# 10_LMS3_RF.net
KiCad netlist of a schematic drawn in Altium Designer
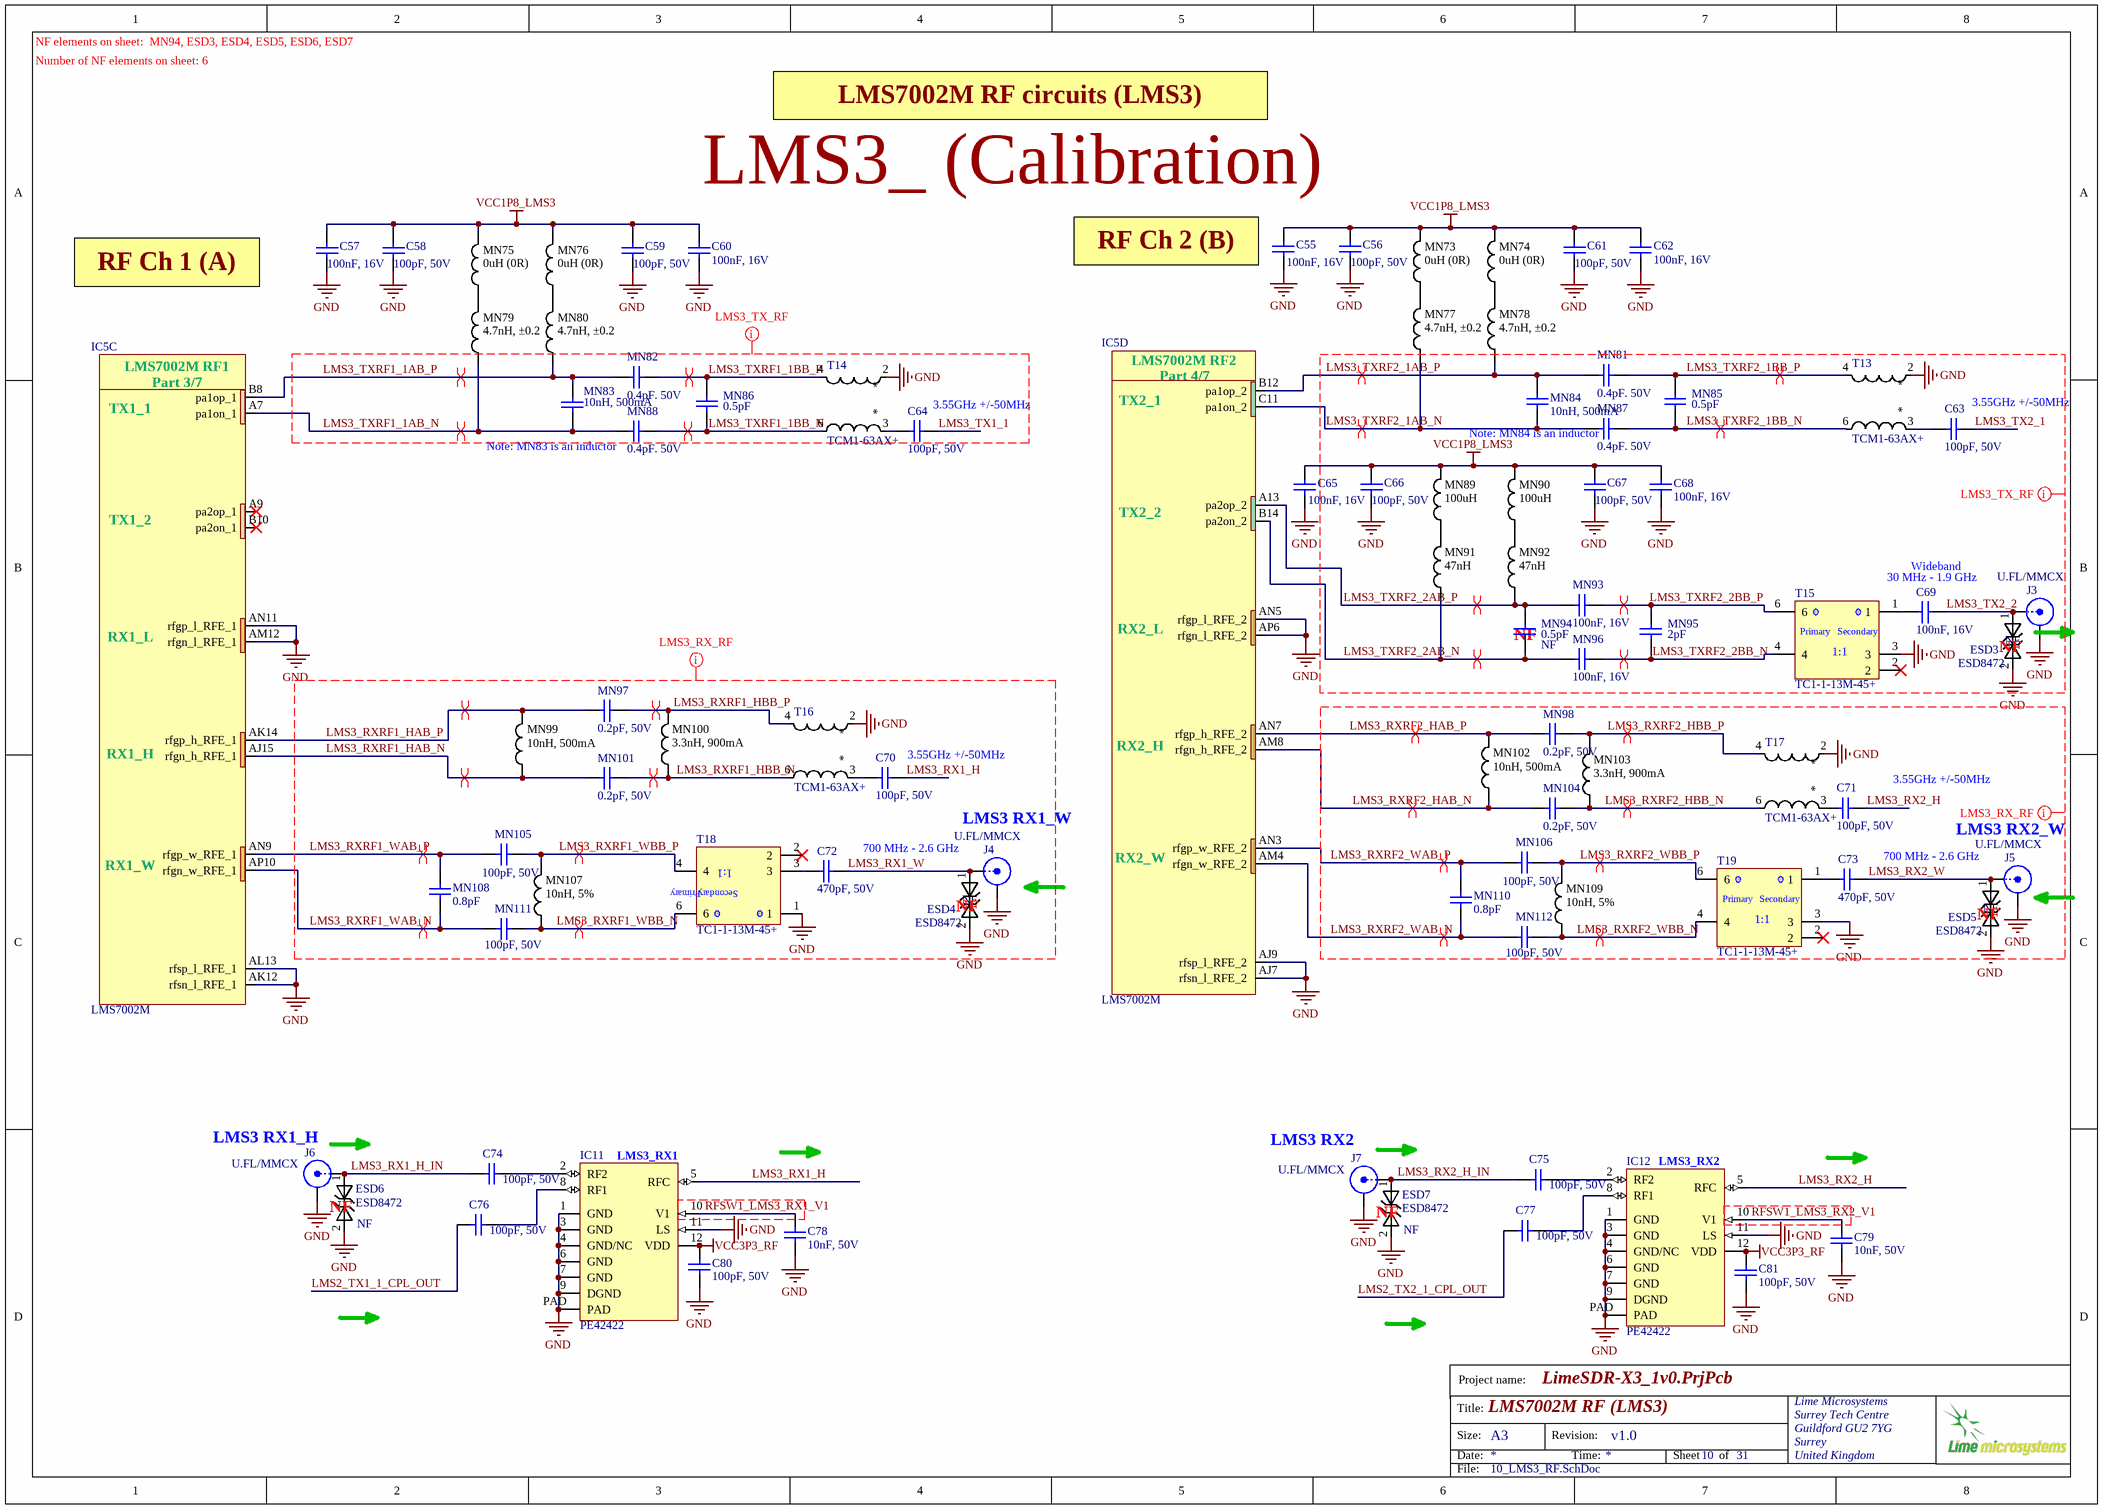
[diagram p0: 10_LMS3_RF.SchDoc]

(export (version "E")
  (design (tool "Eeschema 10.0.6"))
  (components
    (comp (ref "C55")
      (value "100nF, 16V")
      (footprint "CAP0402")
      (fields (field (name "MANUFACTURER") "Murata Electronics") (field (name "TOLERANCE") "10 %"))
      (libsource (lib "") (part "Cap_0402_3"))
    )
    (comp (ref "C56")
      (value "100pF, 50V")
      (footprint "CAP0402")
      (fields (field (name "MANUFACTURER") "Yageo") (field (name "TOLERANCE") "±5%"))
      (libsource (lib "LimeMicroAltiumLib_schLib") (part "Cap_0402"))
    )
    (comp (ref "C57")
      (value "100nF, 16V")
      (footprint "CAP0402")
      (fields (field (name "MANUFACTURER") "Murata Electronics") (field (name "TOLERANCE") "10 %"))
      (libsource (lib "") (part "Cap_0402_7"))
    )
    (comp (ref "C58")
      (value "100pF, 50V")
      (footprint "CAP0402")
      (fields (field (name "MANUFACTURER") "Yageo") (field (name "TOLERANCE") "±5%"))
      (libsource (lib "LimeMicroAltiumLib_schLib") (part "Cap_0402"))
    )
    (comp (ref "C59")
      (value "100pF, 50V")
      (footprint "CAP0402")
      (fields (field (name "MANUFACTURER") "Yageo") (field (name "TOLERANCE") "±5%"))
      (libsource (lib "LimeMicroAltiumLib_schLib") (part "Cap_0402"))
    )
    (comp (ref "C60")
      (value "100nF, 16V")
      (footprint "CAP0402")
      (fields (field (name "MANUFACTURER") "Murata Electronics") (field (name "TOLERANCE") "10 %"))
      (libsource (lib "") (part "Cap_0402_7"))
    )
    (comp (ref "C61")
      (value "100pF, 50V")
      (footprint "CAP0402")
      (fields (field (name "MANUFACTURER") "Yageo") (field (name "TOLERANCE") "±5%"))
      (libsource (lib "LimeMicroAltiumLib_schLib") (part "Cap_0402"))
    )
    (comp (ref "C62")
      (value "100nF, 16V")
      (footprint "CAP0402")
      (fields (field (name "MANUFACTURER") "Murata Electronics") (field (name "TOLERANCE") "10 %"))
      (libsource (lib "") (part "Cap_0402_3"))
    )
    (comp (ref "C63")
      (value "100pF, 50V")
      (footprint "CAP0402")
      (fields (field (name "TOLERANCE") "±5%") (field (name "MANUFACTURER") "Yageo"))
      (libsource (lib "LimeMicroAltiumLib_schLib") (part "Cap_0402"))
    )
    (comp (ref "C64")
      (value "100pF, 50V")
      (footprint "CAP0402")
      (fields (field (name "TOLERANCE") "±5%") (field (name "MANUFACTURER") "Yageo"))
      (libsource (lib "LimeMicroAltiumLib_schLib") (part "Cap_0402"))
    )
    (comp (ref "C65")
      (value "100nF, 16V")
      (footprint "CAP0402")
      (fields (field (name "MANUFACTURER") "Murata Electronics") (field (name "TOLERANCE") "10 %"))
      (libsource (lib "") (part "Cap_0402_4"))
    )
    (comp (ref "C66")
      (value "100pF, 50V")
      (footprint "CAP0402")
      (fields (field (name "MANUFACTURER") "Yageo") (field (name "TOLERANCE") "±5%"))
      (libsource (lib "LimeMicroAltiumLib_schLib") (part "Cap_0402"))
    )
    (comp (ref "C67")
      (value "100pF, 50V")
      (footprint "CAP0402")
      (fields (field (name "MANUFACTURER") "Yageo") (field (name "TOLERANCE") "±5%"))
      (libsource (lib "LimeMicroAltiumLib_schLib") (part "Cap_0402"))
    )
    (comp (ref "C68")
      (value "100nF, 16V")
      (footprint "CAP0402")
      (fields (field (name "MANUFACTURER") "Murata Electronics") (field (name "TOLERANCE") "10 %"))
      (libsource (lib "") (part "Cap_0402_4"))
    )
    (comp (ref "C69")
      (value "100nF, 16V")
      (footprint "CAP0402")
      (fields (field (name "MANUFACTURER") "Murata Electronics") (field (name "TOLERANCE") "10 %"))
      (libsource (lib "") (part "Cap_0402_10"))
    )
    (comp (ref "C70")
      (value "100pF, 50V")
      (footprint "CAP0402")
      (fields (field (name "TOLERANCE") "±5%") (field (name "MANUFACTURER") "Yageo"))
      (libsource (lib "") (part "Cap_0402_8"))
    )
    (comp (ref "C71")
      (value "100pF, 50V")
      (footprint "CAP0402")
      (fields (field (name "TOLERANCE") "±5%") (field (name "MANUFACTURER") "Yageo"))
      (libsource (lib "") (part "Cap_0402_8"))
    )
    (comp (ref "C72")
      (value "470pF, 50V")
      (footprint "CAP0402")
      (fields
        (field (name "MANUFACTURER PART NUMBER") "C1005C0G1H471J050BA")
        (field (name "TOLERANCE") "±5%")
        (field (name "MANUFACTURER") "TDK Corporation")
      )
      (libsource (lib "") (part "Cap_0402_5"))
    )
    (comp (ref "C73")
      (value "470pF, 50V")
      (footprint "CAP0402")
      (fields
        (field (name "MANUFACTURER PART NUMBER") "C1005C0G1H471J050BA")
        (field (name "TOLERANCE") "±5%")
        (field (name "MANUFACTURER") "TDK Corporation")
      )
      (libsource (lib "") (part "Cap_0402_5"))
    )
    (comp (ref "C74")
      (value "100pF, 50V")
      (footprint "CAP0402")
      (fields (field (name "TOLERANCE") "±5%") (field (name "MANUFACTURER") "Yageo"))
      (libsource (lib "") (part "Cap_0402_9"))
    )
    (comp (ref "C75")
      (value "100pF, 50V")
      (footprint "CAP0402")
      (fields (field (name "TOLERANCE") "±5%") (field (name "MANUFACTURER") "Yageo"))
      (libsource (lib "") (part "Cap_0402_9"))
    )
    (comp (ref "C76")
      (value "100pF, 50V")
      (footprint "CAP0402")
      (fields (field (name "TOLERANCE") "±5%") (field (name "MANUFACTURER") "Yageo"))
      (libsource (lib "") (part "Cap_0402_9"))
    )
    (comp (ref "C77")
      (value "100pF, 50V")
      (footprint "CAP0402")
      (fields (field (name "TOLERANCE") "±5%") (field (name "MANUFACTURER") "Yageo"))
      (libsource (lib "") (part "Cap_0402_9"))
    )
    (comp (ref "C78")
      (value "10nF, 50V")
      (footprint "CAP0402")
      (fields
        (field (name "MANUFACTURER") "Murata Electronics North America")
        (field (name "TOLERANCE") "±10%")
      )
      (libsource (lib "") (part "Cap_0402_7"))
    )
    (comp (ref "C79")
      (value "10nF, 50V")
      (footprint "CAP0402")
      (fields
        (field (name "MANUFACTURER") "Murata Electronics North America")
        (field (name "TOLERANCE") "±10%")
      )
      (libsource (lib "") (part "Cap_0402_7"))
    )
    (comp (ref "C80")
      (value "100pF, 50V")
      (footprint "CAP0402")
      (fields (field (name "TOLERANCE") "±5%") (field (name "MANUFACTURER") "Yageo"))
      (libsource (lib "") (part "Cap_0402_11"))
    )
    (comp (ref "C81")
      (value "100pF, 50V")
      (footprint "CAP0402")
      (fields (field (name "TOLERANCE") "±5%") (field (name "MANUFACTURER") "Yageo"))
      (libsource (lib "") (part "Cap_0402_11"))
    )
    (comp (ref "ESD3")
      (value "ESD8472")
      (footprint "ESD8472_X3DFN2")
      (fields (field (name "MANUFACTURER") "ON Semiconductor") (field (name "ASSEMBLY INFO") "NF"))
      (libsource (lib "LimeMicroAltiumLib_schLib") (part "ESD8472"))
    )
    (comp (ref "ESD4")
      (value "ESD8472")
      (footprint "ESD8472_X3DFN2")
      (fields (field (name "MANUFACTURER") "ON Semiconductor") (field (name "ASSEMBLY INFO") "NF"))
      (libsource (lib "LimeMicroAltiumLib_schLib") (part "ESD8472"))
    )
    (comp (ref "ESD5")
      (value "ESD8472")
      (footprint "ESD8472_X3DFN2")
      (fields (field (name "MANUFACTURER") "ON Semiconductor") (field (name "ASSEMBLY INFO") "NF"))
      (libsource (lib "LimeMicroAltiumLib_schLib") (part "ESD8472"))
    )
    (comp (ref "ESD6")
      (value "ESD8472")
      (footprint "ESD8472_X3DFN2")
      (fields (field (name "MANUFACTURER") "ON Semiconductor") (field (name "ASSEMBLY INFO") "NF"))
      (libsource (lib "LimeMicroAltiumLib_schLib") (part "ESD8472"))
    )
    (comp (ref "ESD7")
      (value "ESD8472")
      (footprint "ESD8472_X3DFN2")
      (fields (field (name "MANUFACTURER") "ON Semiconductor") (field (name "ASSEMBLY INFO") "NF"))
      (libsource (lib "LimeMicroAltiumLib_schLib") (part "ESD8472"))
    )
    (comp (ref "IC5")
      (value "LMS7002M")
      (footprint "LMS7002M_v5")
      (description "Schematic symbol revision 4. Default footprint - 0.31mm pad")
      (fields (field (name "MANUFACTURER") "Lime Microsystems"))
      (libsource (lib "LimeMicroAltiumLib_schLib_r04") (part "LMS7002Mr4"))
    )
    (comp (ref "IC11")
      (value "PE42422")
      (footprint "PE42422_QFN12")
      (fields (field (name "MANUFACTURER") "Peregrine Semiconductor"))
      (libsource (lib "LimeMicroAltiumLib_schLib") (part "PE42422"))
    )
    (comp (ref "IC12")
      (value "PE42422")
      (footprint "PE42422_QFN12")
      (fields (field (name "MANUFACTURER") "Peregrine Semiconductor"))
      (libsource (lib "LimeMicroAltiumLib_schLib") (part "PE42422"))
    )
    (comp (ref "J3")
      (value "U.FL/MMCX")
      (footprint "MMCX_UFL_conn_m")
      (description "CONN UMC RCPT STR 50 OHM SMD")
      (fields (field (name "MANUFACTURER") "Amphenol RF"))
      (libsource (lib "LimeMicroAltiumLib_schLib") (part "RF_IF_connector"))
    )
    (comp (ref "J4")
      (value "U.FL/MMCX")
      (footprint "MMCX_UFL_conn_m")
      (description "CONN UMC RCPT STR 50 OHM SMD")
      (fields (field (name "MANUFACTURER") "Amphenol RF"))
      (libsource (lib "LimeMicroAltiumLib_schLib") (part "RF_IF_connector"))
    )
    (comp (ref "J5")
      (value "U.FL/MMCX")
      (footprint "MMCX_UFL_conn_m")
      (description "CONN UMC RCPT STR 50 OHM SMD")
      (fields (field (name "MANUFACTURER") "Amphenol RF"))
      (libsource (lib "LimeMicroAltiumLib_schLib") (part "RF_IF_connector"))
    )
    (comp (ref "J6")
      (value "U.FL/MMCX")
      (footprint "MMCX_UFL_conn_m")
      (description "CONN UMC RCPT STR 50 OHM SMD")
      (fields (field (name "MANUFACTURER") "Amphenol RF"))
      (libsource (lib "LimeMicroAltiumLib_schLib") (part "RF_IF_connector"))
    )
    (comp (ref "J7")
      (value "U.FL/MMCX")
      (footprint "MMCX_UFL_conn_m")
      (description "CONN UMC RCPT STR 50 OHM SMD")
      (fields (field (name "MANUFACTURER") "Amphenol RF"))
      (libsource (lib "LimeMicroAltiumLib_schLib") (part "RF_IF_connector"))
    )
    (comp (ref "MN73")
      (value "0uH (0R)")
      (footprint "RES0603")
      (fields
        (field (name "MANUFACTURER") "Panasonic Electronic Components")
        (field (name "MANUFACTURER PART NUMBER") "ERJ-3GEY0R00V")
        (field (name "TOLERANCE") "Jumper")
      )
      (libsource (lib "LimeMicroAltiumLib_schLib") (part "Inductor_0603"))
    )
    (comp (ref "MN74")
      (value "0uH (0R)")
      (footprint "RES0603")
      (fields
        (field (name "MANUFACTURER") "Panasonic Electronic Components")
        (field (name "MANUFACTURER PART NUMBER") "ERJ-3GEY0R00V")
        (field (name "TOLERANCE") "Jumper")
      )
      (libsource (lib "LimeMicroAltiumLib_schLib") (part "Inductor_0603"))
    )
    (comp (ref "MN75")
      (value "0uH (0R)")
      (footprint "RES0603")
      (fields
        (field (name "MANUFACTURER") "Panasonic Electronic Components")
        (field (name "MANUFACTURER PART NUMBER") "ERJ-3GEY0R00V")
        (field (name "TOLERANCE") "Jumper")
      )
      (libsource (lib "LimeMicroAltiumLib_schLib") (part "Inductor_0603"))
    )
    (comp (ref "MN76")
      (value "0uH (0R)")
      (footprint "RES0603")
      (fields
        (field (name "MANUFACTURER") "Panasonic Electronic Components")
        (field (name "MANUFACTURER PART NUMBER") "ERJ-3GEY0R00V")
        (field (name "TOLERANCE") "Jumper")
      )
      (libsource (lib "LimeMicroAltiumLib_schLib") (part "Inductor_0603"))
    )
    (comp (ref "MN77")
      (value "4.7nH, ±0.2")
      (footprint "RES0402")
      (fields (field (name "MANUFACTURER") "Murata"))
      (libsource (lib "LimeMicroAltiumLib_schLib") (part "Inductor_0603"))
    )
    (comp (ref "MN78")
      (value "4.7nH, ±0.2")
      (footprint "RES0402")
      (fields (field (name "MANUFACTURER") "Murata"))
      (libsource (lib "LimeMicroAltiumLib_schLib") (part "Inductor_0603"))
    )
    (comp (ref "MN79")
      (value "4.7nH, ±0.2")
      (footprint "RES0402")
      (fields (field (name "MANUFACTURER") "Murata"))
      (libsource (lib "LimeMicroAltiumLib_schLib") (part "Inductor_0603"))
    )
    (comp (ref "MN80")
      (value "4.7nH, ±0.2")
      (footprint "RES0402")
      (fields (field (name "MANUFACTURER") "Murata"))
      (libsource (lib "LimeMicroAltiumLib_schLib") (part "Inductor_0603"))
    )
    (comp (ref "MN81")
      (value "0.4pF. 50V")
      (footprint "CAP0402")
      (fields (field (name "MANUFACTURER") "Murata"))
      (libsource (lib "") (part "Cap_0402_4"))
    )
    (comp (ref "MN82")
      (value "0.4pF. 50V")
      (footprint "CAP0402")
      (fields (field (name "MANUFACTURER") "Murata"))
      (libsource (lib "") (part "Cap_0402_4"))
    )
    (comp (ref "MN83")
      (value "10nH, 500mA")
      (footprint "CAP0402")
      (fields (field (name "MANUFACTURER") "Murata") (field (name "TOLERANCE") "2%"))
      (libsource (lib "") (part "Cap_0402_7"))
    )
    (comp (ref "MN84")
      (value "10nH, 500mA")
      (footprint "CAP0402")
      (fields (field (name "MANUFACTURER") "Murata") (field (name "TOLERANCE") "2%"))
      (libsource (lib "") (part "Cap_0402_7"))
    )
    (comp (ref "MN85")
      (value "0.5pF")
      (footprint "CAP0402")
      (fields (field (name "TOLERANCE") "±0.25pF") (field (name "MANUFACTURER") "Yageo"))
      (libsource (lib "") (part "Cap_0402_6"))
    )
    (comp (ref "MN86")
      (value "0.5pF")
      (footprint "CAP0402")
      (fields (field (name "TOLERANCE") "±0.25pF") (field (name "MANUFACTURER") "Yageo"))
      (libsource (lib "") (part "Cap_0402_6"))
    )
    (comp (ref "MN87")
      (value "0.4pF. 50V")
      (footprint "CAP0402")
      (fields (field (name "MANUFACTURER") "Murata"))
      (libsource (lib "") (part "Cap_0402_2"))
    )
    (comp (ref "MN88")
      (value "0.4pF. 50V")
      (footprint "CAP0402")
      (fields (field (name "MANUFACTURER") "Murata"))
      (libsource (lib "") (part "Cap_0402_2"))
    )
    (comp (ref "MN89")
      (value "100uH")
      (footprint "RES0603")
      (fields
        (field (name "MANUFACTURER") "TDK Corporation")
        (field (name "MANUFACTURER PART NUMBER") "GLFR1608T101M-LR")
        (field (name "TOLERANCE") "±20%")
      )
      (libsource (lib "") (part "Inductor_0603_2"))
    )
    (comp (ref "MN90")
      (value "100uH")
      (footprint "RES0603")
      (fields
        (field (name "MANUFACTURER") "TDK Corporation")
        (field (name "MANUFACTURER PART NUMBER") "GLFR1608T101M-LR")
        (field (name "TOLERANCE") "±20%")
      )
      (libsource (lib "") (part "Inductor_0603_2"))
    )
    (comp (ref "MN91")
      (value "47nH")
      (footprint "RES0402")
      (fields (field (name "MANUFACTURER") "COILCRAFT"))
      (libsource (lib "") (part "Inductor_0603_2"))
    )
    (comp (ref "MN92")
      (value "47nH")
      (footprint "RES0402")
      (fields (field (name "MANUFACTURER") "COILCRAFT"))
      (libsource (lib "") (part "Inductor_0603_2"))
    )
    (comp (ref "MN93")
      (value "100nF, 16V")
      (footprint "CAP0402")
      (fields (field (name "MANUFACTURER") "Murata Electronics") (field (name "TOLERANCE") "10 %"))
      (libsource (lib "") (part "Cap_0402_3"))
    )
    (comp (ref "MN94")
      (value "0.5pF")
      (footprint "CAP0402")
      (fields
        (field (name "ASSEMBLY INFO") "NF")
        (field (name "TOLERANCE") "±0.25pF")
        (field (name "MANUFACTURER") "Yageo")
      )
      (libsource (lib "") (part "Cap_0402_4"))
    )
    (comp (ref "MN95")
      (value "2pF")
      (footprint "CAP0402")
      (fields (field (name "MANUFACTURER PART NUMBER") "04025U2R0BAT2A") (field (name "MANUFACTURER") "AVX"))
      (libsource (lib "") (part "Cap_0402_4"))
    )
    (comp (ref "MN96")
      (value "100nF, 16V")
      (footprint "CAP0402")
      (fields (field (name "MANUFACTURER") "Murata Electronics") (field (name "TOLERANCE") "10 %"))
      (libsource (lib "") (part "Cap_0402_12"))
    )
    (comp (ref "MN97")
      (value "0.2pF, 50V")
      (footprint "CAP0402")
      (fields (field (name "MANUFACTURER") "Murata"))
      (libsource (lib "") (part "Cap_0402_1"))
    )
    (comp (ref "MN98")
      (value "0.2pF, 50V")
      (footprint "CAP0402")
      (fields (field (name "MANUFACTURER") "Murata"))
      (libsource (lib "") (part "Cap_0402_1"))
    )
    (comp (ref "MN99")
      (value "10nH, 500mA")
      (footprint "RES0402")
      (fields (field (name "MANUFACTURER") "Murata") (field (name "TOLERANCE") "2%"))
      (libsource (lib "") (part "Inductor_0603_2"))
    )
    (comp (ref "MN100")
      (value "3.3nH, 900mA")
      (footprint "RES0402")
      (fields (field (name "MANUFACTURER") "Murata"))
      (libsource (lib "") (part "Inductor_0603_1"))
    )
    (comp (ref "MN101")
      (value "0.2pF, 50V")
      (footprint "CAP0402")
      (fields (field (name "MANUFACTURER") "Murata"))
      (libsource (lib "") (part "Cap_0402_1"))
    )
    (comp (ref "MN102")
      (value "10nH, 500mA")
      (footprint "RES0402")
      (fields (field (name "MANUFACTURER") "Murata") (field (name "TOLERANCE") "2%"))
      (libsource (lib "") (part "Inductor_0603_2"))
    )
    (comp (ref "MN103")
      (value "3.3nH, 900mA")
      (footprint "RES0402")
      (fields (field (name "MANUFACTURER") "Murata"))
      (libsource (lib "") (part "Inductor_0603_1"))
    )
    (comp (ref "MN104")
      (value "0.2pF, 50V")
      (footprint "CAP0402")
      (fields (field (name "MANUFACTURER") "Murata"))
      (libsource (lib "") (part "Cap_0402_1"))
    )
    (comp (ref "MN105")
      (value "100pF, 50V")
      (footprint "CAP0402")
      (fields (field (name "TOLERANCE") "±5%") (field (name "MANUFACTURER") "Yageo"))
      (libsource (lib "") (part "Cap_0402_5"))
    )
    (comp (ref "MN106")
      (value "100pF, 50V")
      (footprint "CAP0402")
      (fields (field (name "TOLERANCE") "±5%") (field (name "MANUFACTURER") "Yageo"))
      (libsource (lib "") (part "Cap_0402_5"))
    )
    (comp (ref "MN107")
      (value "10nH, 5%")
      (footprint "RES0402")
      (fields (field (name "MANUFACTURER") "COILCRAFT"))
      (libsource (lib "") (part "Inductor_0603_3"))
    )
    (comp (ref "MN108")
      (value "0.8pF")
      (footprint "CAP0402")
      (fields
        (field (name "TOLERANCE") "±0.1pF")
        (field (name "MANUFACTURER") "Murata Electronics North America")
        (field (name "MANUFACTURER PART NUMBER") "GRM1555C1HR80BA01D")
      )
      (libsource (lib "") (part "Cap_0402_5"))
    )
    (comp (ref "MN109")
      (value "10nH, 5%")
      (footprint "RES0402")
      (fields (field (name "MANUFACTURER") "COILCRAFT"))
      (libsource (lib "") (part "Inductor_0603_3"))
    )
    (comp (ref "MN110")
      (value "0.8pF")
      (footprint "CAP0402")
      (fields
        (field (name "TOLERANCE") "±0.1pF")
        (field (name "MANUFACTURER") "Murata Electronics North America")
        (field (name "MANUFACTURER PART NUMBER") "GRM1555C1HR80BA01D")
      )
      (libsource (lib "") (part "Cap_0402_5"))
    )
    (comp (ref "MN111")
      (value "100pF, 50V")
      (footprint "CAP0402")
      (fields (field (name "TOLERANCE") "±5%") (field (name "MANUFACTURER") "Yageo"))
      (libsource (lib "") (part "Cap_0402_5"))
    )
    (comp (ref "MN112")
      (value "100pF, 50V")
      (footprint "CAP0402")
      (fields (field (name "TOLERANCE") "±5%") (field (name "MANUFACTURER") "Yageo"))
      (libsource (lib "") (part "Cap_0402_5"))
    )
    (comp (ref "T13")
      (value "TCM1-63AX+")
      (footprint "TCM1-63AX+_v2")
      (fields (field (name "MANUFACTURER") "Mini-circuits"))
      (libsource (lib "") (part "Balun_v2_1"))
    )
    (comp (ref "T14")
      (value "TCM1-63AX+")
      (footprint "TCM1-63AX+_v2")
      (fields (field (name "MANUFACTURER") "Mini-circuits"))
      (libsource (lib "") (part "Balun_v2_1"))
    )
    (comp (ref "T15")
      (value "TC1-1-13M-45+")
      (footprint "TC1-1-13MA+_JA4220-AL_")
      (fields (field (name "MANUFACTURER") "Minicircuits"))
      (libsource (lib "") (part "TC1-1-13M+_1"))
    )
    (comp (ref "T16")
      (value "TCM1-63AX+")
      (footprint "TCM1-63AX+_v2")
      (fields (field (name "MANUFACTURER") "Mini-circuits"))
      (libsource (lib "LimeMicroAltiumLib_schLib") (part "Balun_v2"))
    )
    (comp (ref "T17")
      (value "TCM1-63AX+")
      (footprint "TCM1-63AX+_v2")
      (fields (field (name "MANUFACTURER") "Mini-circuits"))
      (libsource (lib "LimeMicroAltiumLib_schLib") (part "Balun_v2"))
    )
    (comp (ref "T18")
      (value "TC1-1-13M-45+")
      (footprint "TC1-1-13MA+_JA4220-AL_")
      (fields (field (name "MANUFACTURER") "Minicircuits"))
      (libsource (lib "LimeMicroAltiumLib_schLib") (part "TC1-1-13M+"))
    )
    (comp (ref "T19")
      (value "TC1-1-13M-45+")
      (footprint "TC1-1-13MA+_JA4220-AL_")
      (fields (field (name "MANUFACTURER") "Minicircuits"))
      (libsource (lib "") (part "TC1-1-13M+_1"))
    )
  )
  (nets
    (net (code "1") (name "/LMS2_TX1_1_CPL_OUT") (class "Default")
      (node (ref "C76") (pin "2") (pinfunction "2_2") (pintype "passive"))
    )
    (net (code "2") (name "/LMS2_TX2_1_CPL_OUT") (class "Default")
      (node (ref "C77") (pin "2") (pinfunction "2_2") (pintype "passive"))
    )
    (net (code "3") (name "/LMS3_RX1_H") (class "Default")
      (node (ref "C70") (pin "1") (pinfunction "1_1") (pintype "passive"))
      (node (ref "IC11") (pin "5") (pinfunction "RFC_5") (pintype "bidirectional"))
    )
    (net (code "4") (name "/LMS3_RX1_H_IN") (class "Default")
      (node (ref "C74") (pin "2") (pinfunction "2_2") (pintype "passive"))
      (node (ref "ESD6") (pin "1") (pinfunction "1_1") (pintype "passive"))
      (node (ref "J6") (pin "1") (pinfunction "X_1") (pintype "passive"))
    )
    (net (code "5") (name "/LMS3_RX1_W") (class "Default")
      (node (ref "C72") (pin "1") (pinfunction "1_1") (pintype "passive"))
      (node (ref "ESD4") (pin "1") (pinfunction "1_1") (pintype "passive"))
      (node (ref "J4") (pin "1") (pinfunction "X_1") (pintype "passive"))
    )
    (net (code "6") (name "/LMS3_RX2_H") (class "Default")
      (node (ref "C71") (pin "1") (pinfunction "1_1") (pintype "passive"))
      (node (ref "IC12") (pin "5") (pinfunction "RFC_5") (pintype "bidirectional"))
    )
    (net (code "7") (name "/LMS3_RX2_H_IN") (class "Default")
      (node (ref "C75") (pin "2") (pinfunction "2_2") (pintype "passive"))
      (node (ref "ESD7") (pin "1") (pinfunction "1_1") (pintype "passive"))
      (node (ref "J7") (pin "1") (pinfunction "X_1") (pintype "passive"))
    )
    (net (code "8") (name "/LMS3_RX2_W") (class "Default")
      (node (ref "C73") (pin "1") (pinfunction "1_1") (pintype "passive"))
      (node (ref "ESD5") (pin "1") (pinfunction "1_1") (pintype "passive"))
      (node (ref "J5") (pin "1") (pinfunction "X_1") (pintype "passive"))
    )
    (net (code "9") (name "/LMS3_RXRF1_HAB_N") (class "Default")
      (node (ref "IC5") (pin "AJ15") (pinfunction "rfgn_h_RFE_1_AJ15") (pintype "passive"))
      (node (ref "MN101") (pin "2") (pinfunction "2_2") (pintype "passive"))
      (node (ref "MN99") (pin "1") (pinfunction "1_1") (pintype "passive"))
    )
    (net (code "10") (name "/LMS3_RXRF1_HAB_P") (class "Default")
      (node (ref "IC5") (pin "AK14") (pinfunction "rfgp_h_RFE_1_AK14") (pintype "passive"))
      (node (ref "MN97") (pin "2") (pinfunction "2_2") (pintype "passive"))
      (node (ref "MN99") (pin "2") (pinfunction "2_2") (pintype "passive"))
    )
    (net (code "11") (name "/LMS3_RXRF1_HBB_N") (class "Default")
      (node (ref "MN100") (pin "1") (pinfunction "1_1") (pintype "passive"))
      (node (ref "MN101") (pin "1") (pinfunction "1_1") (pintype "passive"))
      (node (ref "T16") (pin "6") (pinfunction "6_6") (pintype "passive"))
    )
    (net (code "12") (name "/LMS3_RXRF1_HBB_P") (class "Default")
      (node (ref "MN100") (pin "2") (pinfunction "2_2") (pintype "passive"))
      (node (ref "MN97") (pin "1") (pinfunction "1_1") (pintype "passive"))
      (node (ref "T16") (pin "4") (pinfunction "4_4") (pintype "passive"))
    )
    (net (code "13") (name "/LMS3_RXRF1_WAB_N") (class "Default")
      (node (ref "IC5") (pin "AP10") (pinfunction "rfgn_w_RFE_1_AP10") (pintype "passive"))
      (node (ref "MN108") (pin "2") (pinfunction "2_2") (pintype "passive"))
      (node (ref "MN111") (pin "2") (pinfunction "2_2") (pintype "passive"))
    )
    (net (code "14") (name "/LMS3_RXRF1_WAB_P") (class "Default")
      (node (ref "IC5") (pin "AN9") (pinfunction "rfgp_w_RFE_1_AN9") (pintype "passive"))
      (node (ref "MN105") (pin "2") (pinfunction "2_2") (pintype "passive"))
      (node (ref "MN108") (pin "1") (pinfunction "1_1") (pintype "passive"))
    )
    (net (code "15") (name "/LMS3_RXRF1_WBB_N") (class "Default")
      (node (ref "MN107") (pin "1") (pinfunction "1_1") (pintype "passive"))
      (node (ref "MN111") (pin "1") (pinfunction "1_1") (pintype "passive"))
      (node (ref "T18") (pin "6") (pinfunction "6_6") (pintype "passive"))
    )
    (net (code "16") (name "/LMS3_RXRF1_WBB_P") (class "Default")
      (node (ref "MN105") (pin "1") (pinfunction "1_1") (pintype "passive"))
      (node (ref "MN107") (pin "2") (pinfunction "2_2") (pintype "passive"))
      (node (ref "T18") (pin "4") (pinfunction "4_4") (pintype "passive"))
    )
    (net (code "18") (name "/LMS3_RXRF2_HAB_P") (class "Default")
      (node (ref "IC5") (pin "AN7") (pinfunction "rfgp_h_RFE_2_AN7") (pintype "passive"))
      (node (ref "MN102") (pin "2") (pinfunction "2_2") (pintype "passive"))
      (node (ref "MN98") (pin "2") (pinfunction "2_2") (pintype "passive"))
    )
    (net (code "19") (name "/LMS3_RXRF2_HBB_N") (class "Default")
      (node (ref "MN103") (pin "1") (pinfunction "1_1") (pintype "passive"))
      (node (ref "MN104") (pin "1") (pinfunction "1_1") (pintype "passive"))
      (node (ref "T17") (pin "6") (pinfunction "6_6") (pintype "passive"))
    )
    (net (code "20") (name "/LMS3_RXRF2_HBB_P") (class "Default")
      (node (ref "MN103") (pin "2") (pinfunction "2_2") (pintype "passive"))
      (node (ref "MN98") (pin "1") (pinfunction "1_1") (pintype "passive"))
      (node (ref "T17") (pin "4") (pinfunction "4_4") (pintype "passive"))
    )
    (net (code "21") (name "/LMS3_RXRF2_WAB_N") (class "Default")
      (node (ref "IC5") (pin "AM4") (pinfunction "rfgn_w_RFE_2_AM4") (pintype "passive"))
      (node (ref "MN110") (pin "2") (pinfunction "2_2") (pintype "passive"))
      (node (ref "MN112") (pin "2") (pinfunction "2_2") (pintype "passive"))
    )
    (net (code "22") (name "/LMS3_RXRF2_WAB_P") (class "Default")
      (node (ref "IC5") (pin "AN3") (pinfunction "rfgp_w_RFE_2_AN3") (pintype "passive"))
      (node (ref "MN106") (pin "2") (pinfunction "2_2") (pintype "passive"))
      (node (ref "MN110") (pin "1") (pinfunction "1_1") (pintype "passive"))
    )
    (net (code "23") (name "/LMS3_RXRF2_WBB_N") (class "Default")
      (node (ref "MN109") (pin "1") (pinfunction "1_1") (pintype "passive"))
      (node (ref "MN112") (pin "1") (pinfunction "1_1") (pintype "passive"))
      (node (ref "T19") (pin "4") (pinfunction "4_4") (pintype "passive"))
    )
    (net (code "24") (name "/LMS3_RXRF2_WBB_P") (class "Default")
      (node (ref "MN106") (pin "1") (pinfunction "1_1") (pintype "passive"))
      (node (ref "MN109") (pin "2") (pinfunction "2_2") (pintype "passive"))
      (node (ref "T19") (pin "6") (pinfunction "6_6") (pintype "passive"))
    )
    (net (code "25") (name "/LMS3_TX1_1") (class "Default")
      (node (ref "C64") (pin "1") (pinfunction "1_1") (pintype "passive"))
    )
    (net (code "26") (name "/LMS3_TX2_1") (class "Default")
      (node (ref "C63") (pin "1") (pinfunction "1_1") (pintype "passive"))
    )
    (net (code "27") (name "/LMS3_TX2_2") (class "Default")
      (node (ref "C69") (pin "1") (pinfunction "1_1") (pintype "passive"))
      (node (ref "ESD3") (pin "1") (pinfunction "1_1") (pintype "passive"))
      (node (ref "J3") (pin "1") (pinfunction "X_1") (pintype "passive"))
    )
    (net (code "28") (name "/LMS3_TXRF1_1AB_N") (class "Default")
      (node (ref "IC5") (pin "A7") (pinfunction "pa1on_1_A7") (pintype "passive"))
      (node (ref "MN79") (pin "1") (pinfunction "1_1") (pintype "passive"))
      (node (ref "MN83") (pin "2") (pinfunction "2_2") (pintype "passive"))
      (node (ref "MN88") (pin "2") (pinfunction "2_2") (pintype "passive"))
    )
    (net (code "29") (name "/LMS3_TXRF1_1AB_P") (class "Default")
      (node (ref "IC5") (pin "B8") (pinfunction "pa1op_1_B8") (pintype "passive"))
      (node (ref "MN80") (pin "1") (pinfunction "1_1") (pintype "passive"))
      (node (ref "MN82") (pin "2") (pinfunction "2_2") (pintype "passive"))
      (node (ref "MN83") (pin "1") (pinfunction "1_1") (pintype "passive"))
    )
    (net (code "30") (name "/LMS3_TXRF1_1BB_N") (class "Default")
      (node (ref "MN86") (pin "1") (pinfunction "1_1") (pintype "passive"))
      (node (ref "MN88") (pin "1") (pinfunction "1_1") (pintype "passive"))
      (node (ref "T14") (pin "6") (pinfunction "6_6") (pintype "passive"))
    )
    (net (code "31") (name "/LMS3_TXRF1_1BB_P") (class "Default")
      (node (ref "MN82") (pin "1") (pinfunction "1_1") (pintype "passive"))
      (node (ref "MN86") (pin "2") (pinfunction "2_2") (pintype "passive"))
      (node (ref "T14") (pin "4") (pinfunction "4_4") (pintype "passive"))
    )
    (net (code "32") (name "/LMS3_TXRF2_1AB_N") (class "Default")
      (node (ref "IC5") (pin "C11") (pinfunction "pa1on_2_C11") (pintype "passive"))
      (node (ref "MN77") (pin "1") (pinfunction "1_1") (pintype "passive"))
      (node (ref "MN84") (pin "1") (pinfunction "1_1") (pintype "passive"))
      (node (ref "MN87") (pin "2") (pinfunction "2_2") (pintype "passive"))
    )
    (net (code "33") (name "/LMS3_TXRF2_1AB_P") (class "Default")
      (node (ref "IC5") (pin "B12") (pinfunction "pa1op_2_B12") (pintype "passive"))
      (node (ref "MN78") (pin "1") (pinfunction "1_1") (pintype "passive"))
      (node (ref "MN81") (pin "2") (pinfunction "2_2") (pintype "passive"))
      (node (ref "MN84") (pin "2") (pinfunction "2_2") (pintype "passive"))
    )
    (net (code "34") (name "/LMS3_TXRF2_1BB_N") (class "Default")
      (node (ref "MN85") (pin "1") (pinfunction "1_1") (pintype "passive"))
      (node (ref "MN87") (pin "1") (pinfunction "1_1") (pintype "passive"))
      (node (ref "T13") (pin "6") (pinfunction "6_6") (pintype "passive"))
    )
    (net (code "35") (name "/LMS3_TXRF2_1BB_P") (class "Default")
      (node (ref "MN81") (pin "1") (pinfunction "1_1") (pintype "passive"))
      (node (ref "MN85") (pin "2") (pinfunction "2_2") (pintype "passive"))
      (node (ref "T13") (pin "4") (pinfunction "4_4") (pintype "passive"))
    )
    (net (code "36") (name "/LMS3_TXRF2_2AB_N") (class "Default")
      (node (ref "IC5") (pin "B14") (pinfunction "pa2on_2_B14") (pintype "passive"))
      (node (ref "MN91") (pin "1") (pinfunction "1_1") (pintype "passive"))
      (node (ref "MN94") (pin "1") (pinfunction "1_1") (pintype "passive"))
      (node (ref "MN96") (pin "1") (pinfunction "1_1") (pintype "passive"))
    )
    (net (code "37") (name "/LMS3_TXRF2_2AB_P") (class "Default")
      (node (ref "IC5") (pin "A13") (pinfunction "pa2op_2_A13") (pintype "passive"))
      (node (ref "MN92") (pin "1") (pinfunction "1_1") (pintype "passive"))
      (node (ref "MN93") (pin "2") (pinfunction "2_2") (pintype "passive"))
      (node (ref "MN94") (pin "2") (pinfunction "2_2") (pintype "passive"))
    )
    (net (code "38") (name "/LMS3_TXRF2_2BB_N") (class "Default")
      (node (ref "MN95") (pin "1") (pinfunction "1_1") (pintype "passive"))
      (node (ref "MN96") (pin "2") (pinfunction "2_2") (pintype "passive"))
      (node (ref "T15") (pin "4") (pinfunction "4_4") (pintype "passive"))
    )
    (net (code "39") (name "/LMS3_TXRF2_2BB_P") (class "Default")
      (node (ref "MN93") (pin "1") (pinfunction "1_1") (pintype "passive"))
      (node (ref "MN95") (pin "2") (pinfunction "2_2") (pintype "passive"))
      (node (ref "T15") (pin "6") (pinfunction "6_6") (pintype "passive"))
    )
    (net (code "40") (name "/RFSW1_LMS3_RX1_V1") (class "Default")
      (node (ref "C78") (pin "1") (pinfunction "1_1") (pintype "passive"))
      (node (ref "IC11") (pin "10") (pinfunction "V1_10") (pintype "input"))
    )
    (net (code "41") (name "/RFSW1_LMS3_RX2_V1") (class "Default")
      (node (ref "C79") (pin "1") (pinfunction "1_1") (pintype "passive"))
      (node (ref "IC12") (pin "10") (pinfunction "V1_10") (pintype "input"))
    )
    (net (code "42") (name "GND") (class "Default")
      (node (ref "C55") (pin "1") (pinfunction "1_1") (pintype "passive"))
      (node (ref "C56") (pin "1") (pinfunction "1_1") (pintype "passive"))
      (node (ref "C57") (pin "1") (pinfunction "1_1") (pintype "passive"))
      (node (ref "C58") (pin "1") (pinfunction "1_1") (pintype "passive"))
      (node (ref "C59") (pin "1") (pinfunction "1_1") (pintype "passive"))
      (node (ref "C60") (pin "1") (pinfunction "1_1") (pintype "passive"))
      (node (ref "C61") (pin "1") (pinfunction "1_1") (pintype "passive"))
      (node (ref "C62") (pin "1") (pinfunction "1_1") (pintype "passive"))
      (node (ref "C65") (pin "1") (pinfunction "1_1") (pintype "passive"))
      (node (ref "C66") (pin "1") (pinfunction "1_1") (pintype "passive"))
      (node (ref "C67") (pin "1") (pinfunction "1_1") (pintype "passive"))
      (node (ref "C68") (pin "1") (pinfunction "1_1") (pintype "passive"))
      (node (ref "C78") (pin "2") (pinfunction "2_2") (pintype "passive"))
      (node (ref "C79") (pin "2") (pinfunction "2_2") (pintype "passive"))
      (node (ref "C80") (pin "1") (pinfunction "1_1") (pintype "passive"))
      (node (ref "C81") (pin "1") (pinfunction "1_1") (pintype "passive"))
      (node (ref "ESD3") (pin "2") (pinfunction "2_2") (pintype "passive"))
      (node (ref "ESD4") (pin "2") (pinfunction "2_2") (pintype "passive"))
      (node (ref "ESD5") (pin "2") (pinfunction "2_2") (pintype "passive"))
      (node (ref "ESD6") (pin "2") (pinfunction "2_2") (pintype "passive"))
      (node (ref "ESD7") (pin "2") (pinfunction "2_2") (pintype "passive"))
      (node (ref "IC11") (pin "1") (pinfunction "GND_1") (pintype "passive"))
      (node (ref "IC11") (pin "11") (pinfunction "LS_11") (pintype "input"))
      (node (ref "IC11") (pin "3") (pinfunction "GND_3") (pintype "passive"))
      (node (ref "IC11") (pin "4") (pinfunction "GND/NC_4") (pintype "passive"))
      (node (ref "IC11") (pin "6") (pinfunction "GND_6") (pintype "passive"))
      (node (ref "IC11") (pin "7") (pinfunction "GND_7") (pintype "passive"))
      (node (ref "IC11") (pin "9") (pinfunction "DGND_9") (pintype "passive"))
      (node (ref "IC11") (pin "PAD") (pinfunction "PAD_PAD") (pintype "passive"))
      (node (ref "IC12") (pin "1") (pinfunction "GND_1") (pintype "passive"))
      (node (ref "IC12") (pin "11") (pinfunction "LS_11") (pintype "input"))
      (node (ref "IC12") (pin "3") (pinfunction "GND_3") (pintype "passive"))
      (node (ref "IC12") (pin "4") (pinfunction "GND/NC_4") (pintype "passive"))
      (node (ref "IC12") (pin "6") (pinfunction "GND_6") (pintype "passive"))
      (node (ref "IC12") (pin "7") (pinfunction "GND_7") (pintype "passive"))
      (node (ref "IC12") (pin "9") (pinfunction "DGND_9") (pintype "passive"))
      (node (ref "IC12") (pin "PAD") (pinfunction "PAD_PAD") (pintype "passive"))
      (node (ref "IC5") (pin "AJ7") (pinfunction "rfsn_l_RFE_2_AJ7") (pintype "passive"))
      (node (ref "IC5") (pin "AJ9") (pinfunction "rfsp_l_RFE_2_AJ9") (pintype "passive"))
      (node (ref "IC5") (pin "AK12") (pinfunction "rfsn_l_RFE_1_AK12") (pintype "passive"))
      (node (ref "IC5") (pin "AL13") (pinfunction "rfsp_l_RFE_1_AL13") (pintype "passive"))
      (node (ref "IC5") (pin "AM12") (pinfunction "rfgn_l_RFE_1_AM12") (pintype "passive"))
      (node (ref "IC5") (pin "AN11") (pinfunction "rfgp_l_RFE_1_AN11") (pintype "passive"))
      (node (ref "IC5") (pin "AN5") (pinfunction "rfgp_l_RFE_2_AN5") (pintype "passive"))
      (node (ref "IC5") (pin "AP6") (pinfunction "rfgn_l_RFE_2_AP6") (pintype "passive"))
      (node (ref "J3") (pin "2") (pinfunction "Y_2") (pintype "passive"))
      (node (ref "J4") (pin "2") (pinfunction "Y_2") (pintype "passive"))
      (node (ref "J5") (pin "2") (pinfunction "Y_2") (pintype "passive"))
      (node (ref "J6") (pin "2") (pinfunction "Y_2") (pintype "passive"))
      (node (ref "J7") (pin "2") (pinfunction "Y_2") (pintype "passive"))
      (node (ref "T13") (pin "2") (pinfunction "2_2") (pintype "passive"))
      (node (ref "T14") (pin "2") (pinfunction "2_2") (pintype "passive"))
      (node (ref "T15") (pin "3") (pinfunction "3_3") (pintype "passive"))
      (node (ref "T16") (pin "2") (pinfunction "2_2") (pintype "passive"))
      (node (ref "T17") (pin "2") (pinfunction "2_2") (pintype "passive"))
      (node (ref "T18") (pin "1") (pinfunction "1_1") (pintype "passive"))
      (node (ref "T19") (pin "3") (pinfunction "3_3") (pintype "passive"))
    )
    (net (code "43") (name "Net-(C63-Pad2)") (class "Default")
      (node (ref "C63") (pin "2") (pinfunction "2_2") (pintype "passive"))
      (node (ref "T13") (pin "3") (pinfunction "3_3") (pintype "passive"))
    )
    (net (code "44") (name "Net-(C64-Pad2)") (class "Default")
      (node (ref "C64") (pin "2") (pinfunction "2_2") (pintype "passive"))
      (node (ref "T14") (pin "3") (pinfunction "3_3") (pintype "passive"))
    )
    (net (code "45") (name "Net-(C69-Pad2)") (class "Default")
      (node (ref "C69") (pin "2") (pinfunction "2_2") (pintype "passive"))
      (node (ref "T15") (pin "1") (pinfunction "1_1") (pintype "passive"))
    )
    (net (code "46") (name "Net-(C70-Pad2)") (class "Default")
      (node (ref "C70") (pin "2") (pinfunction "2_2") (pintype "passive"))
      (node (ref "T16") (pin "3") (pinfunction "3_3") (pintype "passive"))
    )
    (net (code "47") (name "Net-(C71-Pad2)") (class "Default")
      (node (ref "C71") (pin "2") (pinfunction "2_2") (pintype "passive"))
      (node (ref "T17") (pin "3") (pinfunction "3_3") (pintype "passive"))
    )
    (net (code "48") (name "Net-(C72-Pad2)") (class "Default")
      (node (ref "C72") (pin "2") (pinfunction "2_2") (pintype "passive"))
      (node (ref "T18") (pin "3") (pinfunction "3_3") (pintype "passive"))
    )
    (net (code "49") (name "Net-(C73-Pad2)") (class "Default")
      (node (ref "C73") (pin "2") (pinfunction "2_2") (pintype "passive"))
      (node (ref "T19") (pin "1") (pinfunction "1_1") (pintype "passive"))
    )
    (net (code "50") (name "Net-(IC5D-rfgn_h_RFE_2)") (class "Default")
      (node (ref "IC5") (pin "AM8") (pinfunction "rfgn_h_RFE_2_AM8") (pintype "passive"))
      (node (ref "MN102") (pin "1") (pinfunction "1_1") (pintype "passive"))
      (node (ref "MN104") (pin "2") (pinfunction "2_2") (pintype "passive"))
    )
    (net (code "51") (name "Net-(IC11-RF1)") (class "Default")
      (node (ref "C76") (pin "1") (pinfunction "1_1") (pintype "passive"))
      (node (ref "IC11") (pin "8") (pinfunction "RF1_8") (pintype "bidirectional"))
    )
    (net (code "52") (name "Net-(IC11-RF2)") (class "Default")
      (node (ref "C74") (pin "1") (pinfunction "1_1") (pintype "passive"))
      (node (ref "IC11") (pin "2") (pinfunction "RF2_2") (pintype "bidirectional"))
    )
    (net (code "53") (name "Net-(IC12-RF1)") (class "Default")
      (node (ref "C77") (pin "1") (pinfunction "1_1") (pintype "passive"))
      (node (ref "IC12") (pin "8") (pinfunction "RF1_8") (pintype "bidirectional"))
    )
    (net (code "54") (name "Net-(IC12-RF2)") (class "Default")
      (node (ref "C75") (pin "1") (pinfunction "1_1") (pintype "passive"))
      (node (ref "IC12") (pin "2") (pinfunction "RF2_2") (pintype "bidirectional"))
    )
    (net (code "55") (name "Net-(MN73-Pad1)") (class "Default")
      (node (ref "MN73") (pin "1") (pinfunction "1_1") (pintype "passive"))
      (node (ref "MN77") (pin "2") (pinfunction "2_2") (pintype "passive"))
    )
    (net (code "56") (name "Net-(MN74-Pad1)") (class "Default")
      (node (ref "MN74") (pin "1") (pinfunction "1_1") (pintype "passive"))
      (node (ref "MN78") (pin "2") (pinfunction "2_2") (pintype "passive"))
    )
    (net (code "57") (name "Net-(MN75-Pad1)") (class "Default")
      (node (ref "MN75") (pin "1") (pinfunction "1_1") (pintype "passive"))
      (node (ref "MN79") (pin "2") (pinfunction "2_2") (pintype "passive"))
    )
    (net (code "58") (name "Net-(MN76-Pad1)") (class "Default")
      (node (ref "MN76") (pin "1") (pinfunction "1_1") (pintype "passive"))
      (node (ref "MN80") (pin "2") (pinfunction "2_2") (pintype "passive"))
    )
    (net (code "59") (name "Net-(MN89-Pad1)") (class "Default")
      (node (ref "MN89") (pin "1") (pinfunction "1_1") (pintype "passive"))
      (node (ref "MN91") (pin "2") (pinfunction "2_2") (pintype "passive"))
    )
    (net (code "60") (name "Net-(MN90-Pad1)") (class "Default")
      (node (ref "MN90") (pin "1") (pinfunction "1_1") (pintype "passive"))
      (node (ref "MN92") (pin "2") (pinfunction "2_2") (pintype "passive"))
    )
    (net (code "61") (name "VCC1P8_LMS3") (class "Default")
      (node (ref "C55") (pin "2") (pinfunction "2_2") (pintype "passive"))
      (node (ref "C56") (pin "2") (pinfunction "2_2") (pintype "passive"))
      (node (ref "C57") (pin "2") (pinfunction "2_2") (pintype "passive"))
      (node (ref "C58") (pin "2") (pinfunction "2_2") (pintype "passive"))
      (node (ref "C59") (pin "2") (pinfunction "2_2") (pintype "passive"))
      (node (ref "C60") (pin "2") (pinfunction "2_2") (pintype "passive"))
      (node (ref "C61") (pin "2") (pinfunction "2_2") (pintype "passive"))
      (node (ref "C62") (pin "2") (pinfunction "2_2") (pintype "passive"))
      (node (ref "C65") (pin "2") (pinfunction "2_2") (pintype "passive"))
      (node (ref "C66") (pin "2") (pinfunction "2_2") (pintype "passive"))
      (node (ref "C67") (pin "2") (pinfunction "2_2") (pintype "passive"))
      (node (ref "C68") (pin "2") (pinfunction "2_2") (pintype "passive"))
      (node (ref "MN73") (pin "2") (pinfunction "2_2") (pintype "passive"))
      (node (ref "MN74") (pin "2") (pinfunction "2_2") (pintype "passive"))
      (node (ref "MN75") (pin "2") (pinfunction "2_2") (pintype "passive"))
      (node (ref "MN76") (pin "2") (pinfunction "2_2") (pintype "passive"))
      (node (ref "MN89") (pin "2") (pinfunction "2_2") (pintype "passive"))
      (node (ref "MN90") (pin "2") (pinfunction "2_2") (pintype "passive"))
    )
    (net (code "62") (name "VCC3P3_RF") (class "Default")
      (node (ref "C80") (pin "2") (pinfunction "2_2") (pintype "passive"))
      (node (ref "C81") (pin "2") (pinfunction "2_2") (pintype "passive"))
      (node (ref "IC11") (pin "12") (pinfunction "VDD_12") (pintype "power_in"))
      (node (ref "IC12") (pin "12") (pinfunction "VDD_12") (pintype "power_in"))
    )
    (net (code "63") (name "unconnected-(IC5C-pa2on_1-PadB10)") (class "Default")
      (node (ref "IC5") (pin "B10") (pinfunction "pa2on_1_B10") (pintype "passive+no_connect"))
    )
    (net (code "64") (name "unconnected-(IC5C-pa2op_1-PadA9)") (class "Default")
      (node (ref "IC5") (pin "A9") (pinfunction "pa2op_1_A9") (pintype "passive+no_connect"))
    )
    (net (code "65") (name "unconnected-(T15-Pad2)") (class "Default")
      (node (ref "T15") (pin "2") (pinfunction "2_2") (pintype "passive+no_connect"))
    )
    (net (code "66") (name "unconnected-(T18-Pad2)") (class "Default")
      (node (ref "T18") (pin "2") (pinfunction "2_2") (pintype "passive+no_connect"))
    )
    (net (code "67") (name "unconnected-(T19-Pad2)") (class "Default")
      (node (ref "T19") (pin "2") (pinfunction "2_2") (pintype "passive+no_connect"))
    )
  )
)
